# Nextronic-Arduino.net
KiCad netlist of a schematic drawn in EAGLE
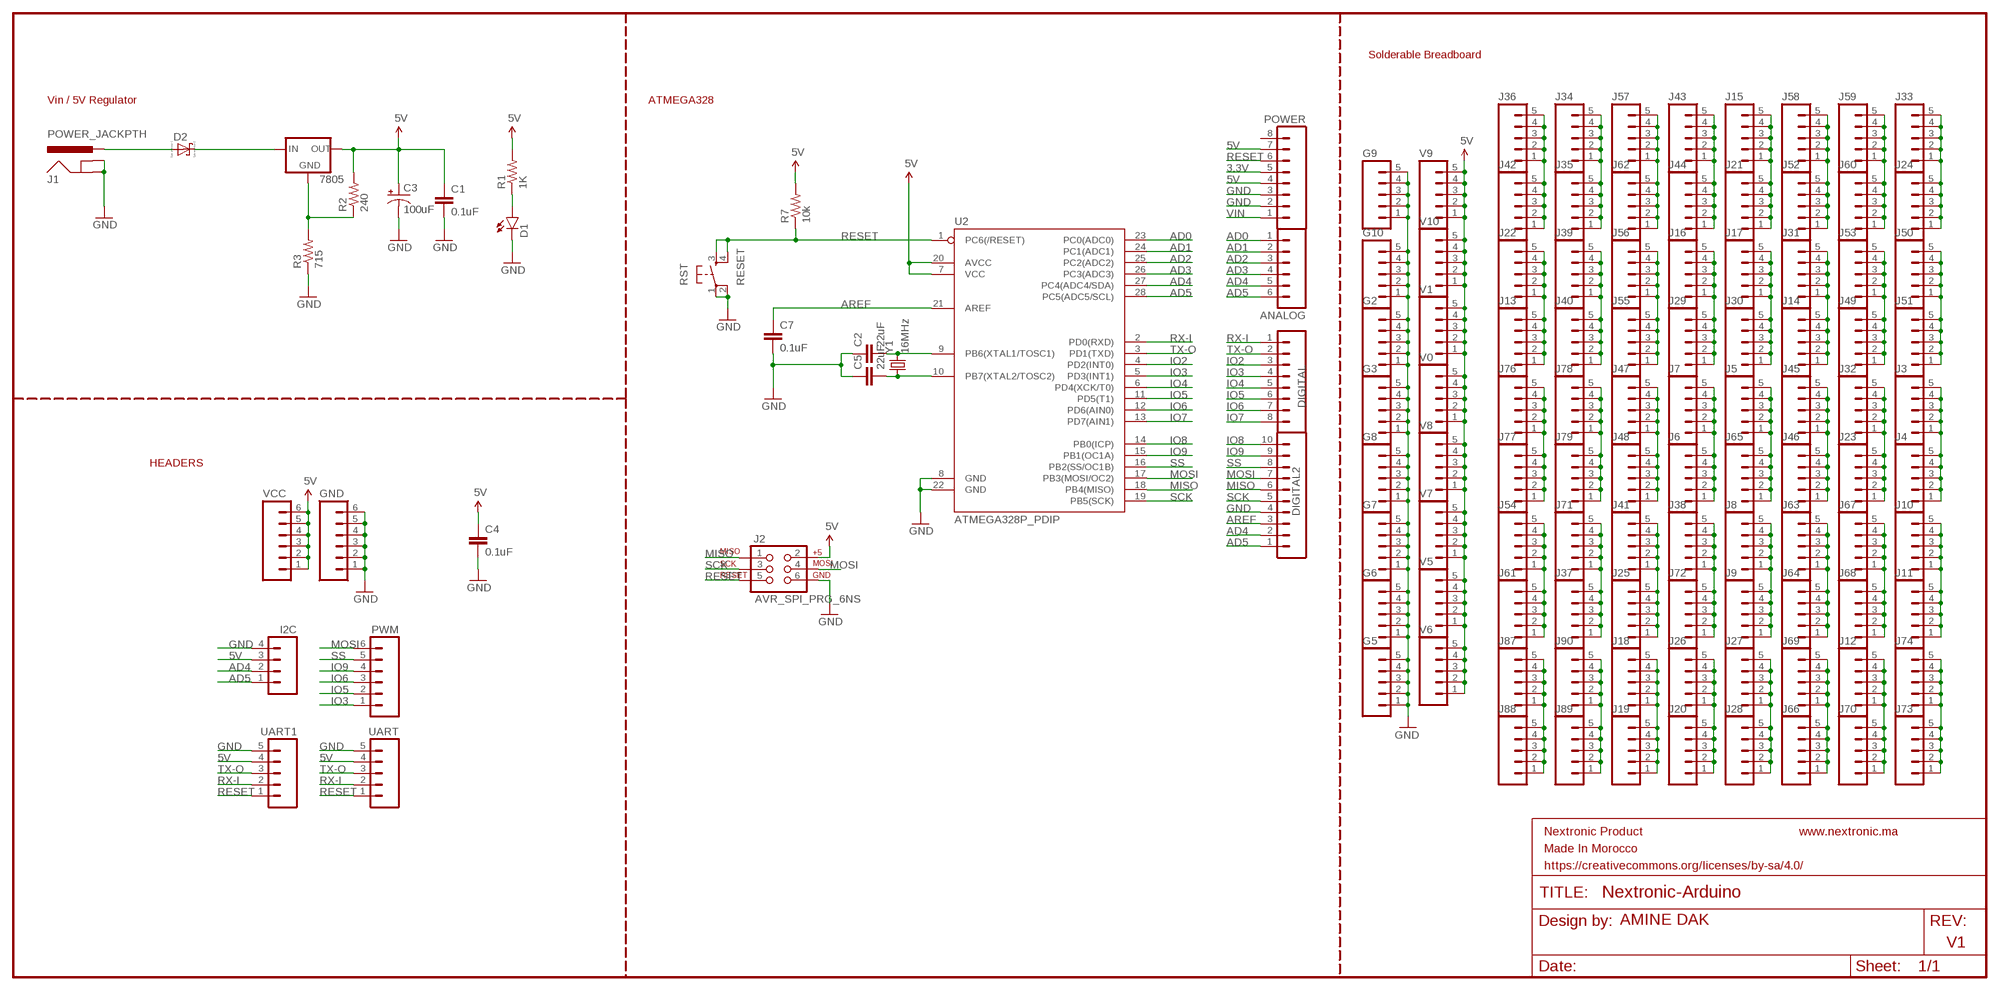
[diagram p0: schematic, sheet 1]

(export (version "E")
  (design (tool "Eeschema 10.0.6"))
  (components
    (comp (ref "7805")
      (value "V_REG_78XX-TO-220")
      (footprint "eagle-import:TO-220-ALT")
      (libsource (lib "eagle-import") (part "V_REG_78XX-TO-220"))
    )
    (comp (ref "ANALOG")
      (value "M06SILK_FEMALE_PTH")
      (footprint "eagle-import:1X06")
      (libsource (lib "eagle-import") (part "M06SILK_FEMALE_PTH"))
    )
    (comp (ref "C1")
      (value "0.1uF")
      (footprint "eagle-import:CAP-PTH-SMALLEZ")
      (fields (field (name "MF") "MULTICOMP") (field (name "MPN") "MCRR25104X7RK0050"))
      (libsource (lib "eagle-import") (part "CAPEZ"))
    )
    (comp (ref "C2")
      (value "22uF")
      (footprint "eagle-import:CAP-PTH-SMALLEZ")
      (fields (field (name "MF") "MULTICOMP") (field (name "MPN") "MCGPR100V226M8X11"))
      (libsource (lib "eagle-import") (part "CAPEZ"))
    )
    (comp (ref "C3")
      (value "100uF")
      (footprint "eagle-import:CPOL-RADIAL-100UF-25V")
      (fields (field (name "MF") "MULTICOMP") (field (name "MPN") "MCGPR25V107M6.3X11"))
      (libsource (lib "eagle-import") (part "CAP_POLPTH1"))
    )
    (comp (ref "C4")
      (value "0.1uF")
      (footprint "eagle-import:CAP-PTH-SMALLEZ")
      (fields (field (name "MF") "MULTICOMP") (field (name "MPN") "MCRR25104X7RK0050"))
      (libsource (lib "eagle-import") (part "CAPEZ"))
    )
    (comp (ref "C5")
      (value "22uF")
      (footprint "eagle-import:CAP-PTH-SMALLEZ")
      (fields (field (name "MF") "MULTICOMP") (field (name "MPN") "MCGPR100V226M8X11"))
      (libsource (lib "eagle-import") (part "CAPEZ"))
    )
    (comp (ref "C7")
      (value "0.1uF")
      (footprint "eagle-import:CAP-PTH-SMALLEZ")
      (fields (field (name "MF") "MULTICOMP") (field (name "MPN") "MCRR25104X7RK0050"))
      (libsource (lib "eagle-import") (part "CAPEZ"))
    )
    (comp (ref "D1")
      (value "LED-3MM-NO_SILK")
      (footprint "eagle-import:LED3MM-NS")
      (libsource (lib "eagle-import") (part "LED-3MM-NO_SILK"))
    )
    (comp (ref "D2")
      (value "SCHOTTKY-DIODEDO35-7")
      (footprint "eagle-import:DIODE_DO35-7")
      (libsource (lib "eagle-import") (part "SCHOTTKY-DIODEDO35-7"))
    )
    (comp (ref "DIGITAL")
      (value "M08SILK_FEMALE_PTH")
      (footprint "eagle-import:1X08")
      (libsource (lib "eagle-import") (part "M08SILK_FEMALE_PTH"))
    )
    (comp (ref "DIGITAL2")
      (value "M10SILK_FEMALE_PTH")
      (footprint "eagle-import:1X10")
      (libsource (lib "eagle-import") (part "M10SILK_FEMALE_PTH"))
    )
    (comp (ref "G2")
      (value "M05PTH")
      (footprint "eagle-import:1X05")
      (libsource (lib "eagle-import") (part "M05PTH"))
    )
    (comp (ref "G3")
      (value "M05PTH")
      (footprint "eagle-import:1X05")
      (libsource (lib "eagle-import") (part "M05PTH"))
    )
    (comp (ref "G5")
      (value "M05PTH")
      (footprint "eagle-import:1X05")
      (libsource (lib "eagle-import") (part "M05PTH"))
    )
    (comp (ref "G6")
      (value "M05PTH")
      (footprint "eagle-import:1X05")
      (libsource (lib "eagle-import") (part "M05PTH"))
    )
    (comp (ref "G7")
      (value "M05PTH")
      (footprint "eagle-import:1X05")
      (libsource (lib "eagle-import") (part "M05PTH"))
    )
    (comp (ref "G8")
      (value "M05PTH")
      (footprint "eagle-import:1X05")
      (libsource (lib "eagle-import") (part "M05PTH"))
    )
    (comp (ref "G9")
      (value "M05PTH")
      (footprint "eagle-import:1X05")
      (libsource (lib "eagle-import") (part "M05PTH"))
    )
    (comp (ref "G10")
      (value "M05PTH")
      (footprint "eagle-import:1X05")
      (libsource (lib "eagle-import") (part "M05PTH"))
    )
    (comp (ref "GND")
      (value "M06SILK_FEMALE_PTH")
      (footprint "eagle-import:1X06")
      (libsource (lib "eagle-import") (part "M06SILK_FEMALE_PTH"))
    )
    (comp (ref "I2C")
      (value "M04PTH")
      (footprint "eagle-import:1X04")
      (libsource (lib "eagle-import") (part "M04PTH"))
    )
    (comp (ref "J1")
      (value "POWER_JACKPTH")
      (footprint "eagle-import:POWER_JACK_PTH")
      (libsource (lib "eagle-import") (part "POWER_JACKPTH"))
    )
    (comp (ref "J2")
      (value "AVR_SPI_PRG_6NS")
      (footprint "eagle-import:2X3-NS")
      (libsource (lib "eagle-import") (part "AVR_SPI_PRG_6NS"))
    )
    (comp (ref "J3")
      (value "M05PTH")
      (footprint "eagle-import:1X05")
      (libsource (lib "eagle-import") (part "M05PTH"))
    )
    (comp (ref "J4")
      (value "M05PTH")
      (footprint "eagle-import:1X05")
      (libsource (lib "eagle-import") (part "M05PTH"))
    )
    (comp (ref "J5")
      (value "M05PTH")
      (footprint "eagle-import:1X05")
      (libsource (lib "eagle-import") (part "M05PTH"))
    )
    (comp (ref "J6")
      (value "M05PTH")
      (footprint "eagle-import:1X05")
      (libsource (lib "eagle-import") (part "M05PTH"))
    )
    (comp (ref "J7")
      (value "M05PTH")
      (footprint "eagle-import:1X05")
      (libsource (lib "eagle-import") (part "M05PTH"))
    )
    (comp (ref "J8")
      (value "M05PTH")
      (footprint "eagle-import:1X05")
      (libsource (lib "eagle-import") (part "M05PTH"))
    )
    (comp (ref "J9")
      (value "M05PTH")
      (footprint "eagle-import:1X05")
      (libsource (lib "eagle-import") (part "M05PTH"))
    )
    (comp (ref "J10")
      (value "M05PTH")
      (footprint "eagle-import:1X05")
      (libsource (lib "eagle-import") (part "M05PTH"))
    )
    (comp (ref "J11")
      (value "M05PTH")
      (footprint "eagle-import:1X05")
      (libsource (lib "eagle-import") (part "M05PTH"))
    )
    (comp (ref "J12")
      (value "M05PTH")
      (footprint "eagle-import:1X05")
      (libsource (lib "eagle-import") (part "M05PTH"))
    )
    (comp (ref "J13")
      (value "M05PTH")
      (footprint "eagle-import:1X05")
      (libsource (lib "eagle-import") (part "M05PTH"))
    )
    (comp (ref "J14")
      (value "M05PTH")
      (footprint "eagle-import:1X05")
      (libsource (lib "eagle-import") (part "M05PTH"))
    )
    (comp (ref "J15")
      (value "M05PTH")
      (footprint "eagle-import:1X05")
      (libsource (lib "eagle-import") (part "M05PTH"))
    )
    (comp (ref "J16")
      (value "M05PTH")
      (footprint "eagle-import:1X05")
      (libsource (lib "eagle-import") (part "M05PTH"))
    )
    (comp (ref "J17")
      (value "M05PTH")
      (footprint "eagle-import:1X05")
      (libsource (lib "eagle-import") (part "M05PTH"))
    )
    (comp (ref "J18")
      (value "M05PTH")
      (footprint "eagle-import:1X05")
      (libsource (lib "eagle-import") (part "M05PTH"))
    )
    (comp (ref "J19")
      (value "M05PTH")
      (footprint "eagle-import:1X05")
      (libsource (lib "eagle-import") (part "M05PTH"))
    )
    (comp (ref "J20")
      (value "M05PTH")
      (footprint "eagle-import:1X05")
      (libsource (lib "eagle-import") (part "M05PTH"))
    )
    (comp (ref "J21")
      (value "M05PTH")
      (footprint "eagle-import:1X05")
      (libsource (lib "eagle-import") (part "M05PTH"))
    )
    (comp (ref "J22")
      (value "M05PTH")
      (footprint "eagle-import:1X05")
      (libsource (lib "eagle-import") (part "M05PTH"))
    )
    (comp (ref "J23")
      (value "M05PTH")
      (footprint "eagle-import:1X05")
      (libsource (lib "eagle-import") (part "M05PTH"))
    )
    (comp (ref "J24")
      (value "M05PTH")
      (footprint "eagle-import:1X05")
      (libsource (lib "eagle-import") (part "M05PTH"))
    )
    (comp (ref "J25")
      (value "M05PTH")
      (footprint "eagle-import:1X05")
      (libsource (lib "eagle-import") (part "M05PTH"))
    )
    (comp (ref "J26")
      (value "M05PTH")
      (footprint "eagle-import:1X05")
      (libsource (lib "eagle-import") (part "M05PTH"))
    )
    (comp (ref "J27")
      (value "M05PTH")
      (footprint "eagle-import:1X05")
      (libsource (lib "eagle-import") (part "M05PTH"))
    )
    (comp (ref "J28")
      (value "M05PTH")
      (footprint "eagle-import:1X05")
      (libsource (lib "eagle-import") (part "M05PTH"))
    )
    (comp (ref "J29")
      (value "M05PTH")
      (footprint "eagle-import:1X05")
      (libsource (lib "eagle-import") (part "M05PTH"))
    )
    (comp (ref "J30")
      (value "M05PTH")
      (footprint "eagle-import:1X05")
      (libsource (lib "eagle-import") (part "M05PTH"))
    )
    (comp (ref "J31")
      (value "M05PTH")
      (footprint "eagle-import:1X05")
      (libsource (lib "eagle-import") (part "M05PTH"))
    )
    (comp (ref "J32")
      (value "M05PTH")
      (footprint "eagle-import:1X05")
      (libsource (lib "eagle-import") (part "M05PTH"))
    )
    (comp (ref "J33")
      (value "M05PTH")
      (footprint "eagle-import:1X05")
      (libsource (lib "eagle-import") (part "M05PTH"))
    )
    (comp (ref "J34")
      (value "M05PTH")
      (footprint "eagle-import:1X05")
      (libsource (lib "eagle-import") (part "M05PTH"))
    )
    (comp (ref "J35")
      (value "M05PTH")
      (footprint "eagle-import:1X05")
      (libsource (lib "eagle-import") (part "M05PTH"))
    )
    (comp (ref "J36")
      (value "M05PTH")
      (footprint "eagle-import:1X05")
      (libsource (lib "eagle-import") (part "M05PTH"))
    )
    (comp (ref "J37")
      (value "M05PTH")
      (footprint "eagle-import:1X05")
      (libsource (lib "eagle-import") (part "M05PTH"))
    )
    (comp (ref "J38")
      (value "M05PTH")
      (footprint "eagle-import:1X05")
      (libsource (lib "eagle-import") (part "M05PTH"))
    )
    (comp (ref "J39")
      (value "M05PTH")
      (footprint "eagle-import:1X05")
      (libsource (lib "eagle-import") (part "M05PTH"))
    )
    (comp (ref "J40")
      (value "M05PTH")
      (footprint "eagle-import:1X05")
      (libsource (lib "eagle-import") (part "M05PTH"))
    )
    (comp (ref "J41")
      (value "M05PTH")
      (footprint "eagle-import:1X05")
      (libsource (lib "eagle-import") (part "M05PTH"))
    )
    (comp (ref "J42")
      (value "M05PTH")
      (footprint "eagle-import:1X05")
      (libsource (lib "eagle-import") (part "M05PTH"))
    )
    (comp (ref "J43")
      (value "M05PTH")
      (footprint "eagle-import:1X05")
      (libsource (lib "eagle-import") (part "M05PTH"))
    )
    (comp (ref "J44")
      (value "M05PTH")
      (footprint "eagle-import:1X05")
      (libsource (lib "eagle-import") (part "M05PTH"))
    )
    (comp (ref "J45")
      (value "M05PTH")
      (footprint "eagle-import:1X05")
      (libsource (lib "eagle-import") (part "M05PTH"))
    )
    (comp (ref "J46")
      (value "M05PTH")
      (footprint "eagle-import:1X05")
      (libsource (lib "eagle-import") (part "M05PTH"))
    )
    (comp (ref "J47")
      (value "M05PTH")
      (footprint "eagle-import:1X05")
      (libsource (lib "eagle-import") (part "M05PTH"))
    )
    (comp (ref "J48")
      (value "M05PTH")
      (footprint "eagle-import:1X05")
      (libsource (lib "eagle-import") (part "M05PTH"))
    )
    (comp (ref "J49")
      (value "M05PTH")
      (footprint "eagle-import:1X05")
      (libsource (lib "eagle-import") (part "M05PTH"))
    )
    (comp (ref "J50")
      (value "M05PTH")
      (footprint "eagle-import:1X05")
      (libsource (lib "eagle-import") (part "M05PTH"))
    )
    (comp (ref "J51")
      (value "M05PTH")
      (footprint "eagle-import:1X05")
      (libsource (lib "eagle-import") (part "M05PTH"))
    )
    (comp (ref "J52")
      (value "M05PTH")
      (footprint "eagle-import:1X05")
      (libsource (lib "eagle-import") (part "M05PTH"))
    )
    (comp (ref "J53")
      (value "M05PTH")
      (footprint "eagle-import:1X05")
      (libsource (lib "eagle-import") (part "M05PTH"))
    )
    (comp (ref "J54")
      (value "M05PTH")
      (footprint "eagle-import:1X05")
      (libsource (lib "eagle-import") (part "M05PTH"))
    )
    (comp (ref "J55")
      (value "M05PTH")
      (footprint "eagle-import:1X05")
      (libsource (lib "eagle-import") (part "M05PTH"))
    )
    (comp (ref "J56")
      (value "M05PTH")
      (footprint "eagle-import:1X05")
      (libsource (lib "eagle-import") (part "M05PTH"))
    )
    (comp (ref "J57")
      (value "M05PTH")
      (footprint "eagle-import:1X05")
      (libsource (lib "eagle-import") (part "M05PTH"))
    )
    (comp (ref "J58")
      (value "M05PTH")
      (footprint "eagle-import:1X05")
      (libsource (lib "eagle-import") (part "M05PTH"))
    )
    (comp (ref "J59")
      (value "M05PTH")
      (footprint "eagle-import:1X05")
      (libsource (lib "eagle-import") (part "M05PTH"))
    )
    (comp (ref "J60")
      (value "M05PTH")
      (footprint "eagle-import:1X05")
      (libsource (lib "eagle-import") (part "M05PTH"))
    )
    (comp (ref "J61")
      (value "M05PTH")
      (footprint "eagle-import:1X05")
      (libsource (lib "eagle-import") (part "M05PTH"))
    )
    (comp (ref "J62")
      (value "M05PTH")
      (footprint "eagle-import:1X05")
      (libsource (lib "eagle-import") (part "M05PTH"))
    )
    (comp (ref "J63")
      (value "M05PTH")
      (footprint "eagle-import:1X05")
      (libsource (lib "eagle-import") (part "M05PTH"))
    )
    (comp (ref "J64")
      (value "M05PTH")
      (footprint "eagle-import:1X05")
      (libsource (lib "eagle-import") (part "M05PTH"))
    )
    (comp (ref "J65")
      (value "M05PTH")
      (footprint "eagle-import:1X05")
      (libsource (lib "eagle-import") (part "M05PTH"))
    )
    (comp (ref "J66")
      (value "M05PTH")
      (footprint "eagle-import:1X05")
      (libsource (lib "eagle-import") (part "M05PTH"))
    )
    (comp (ref "J67")
      (value "M05PTH")
      (footprint "eagle-import:1X05")
      (libsource (lib "eagle-import") (part "M05PTH"))
    )
    (comp (ref "J68")
      (value "M05PTH")
      (footprint "eagle-import:1X05")
      (libsource (lib "eagle-import") (part "M05PTH"))
    )
    (comp (ref "J69")
      (value "M05PTH")
      (footprint "eagle-import:1X05")
      (libsource (lib "eagle-import") (part "M05PTH"))
    )
    (comp (ref "J70")
      (value "M05PTH")
      (footprint "eagle-import:1X05")
      (libsource (lib "eagle-import") (part "M05PTH"))
    )
    (comp (ref "J71")
      (value "M05PTH")
      (footprint "eagle-import:1X05")
      (libsource (lib "eagle-import") (part "M05PTH"))
    )
    (comp (ref "J72")
      (value "M05PTH")
      (footprint "eagle-import:1X05")
      (libsource (lib "eagle-import") (part "M05PTH"))
    )
    (comp (ref "J73")
      (value "M05PTH")
      (footprint "eagle-import:1X05")
      (libsource (lib "eagle-import") (part "M05PTH"))
    )
    (comp (ref "J74")
      (value "M05PTH")
      (footprint "eagle-import:1X05")
      (libsource (lib "eagle-import") (part "M05PTH"))
    )
    (comp (ref "J76")
      (value "M05PTH")
      (footprint "eagle-import:1X05")
      (libsource (lib "eagle-import") (part "M05PTH"))
    )
    (comp (ref "J77")
      (value "M05PTH")
      (footprint "eagle-import:1X05")
      (libsource (lib "eagle-import") (part "M05PTH"))
    )
    (comp (ref "J78")
      (value "M05PTH")
      (footprint "eagle-import:1X05")
      (libsource (lib "eagle-import") (part "M05PTH"))
    )
    (comp (ref "J79")
      (value "M05PTH")
      (footprint "eagle-import:1X05")
      (libsource (lib "eagle-import") (part "M05PTH"))
    )
    (comp (ref "J87")
      (value "M05PTH")
      (footprint "eagle-import:1X05")
      (libsource (lib "eagle-import") (part "M05PTH"))
    )
    (comp (ref "J88")
      (value "M05PTH")
      (footprint "eagle-import:1X05")
      (libsource (lib "eagle-import") (part "M05PTH"))
    )
    (comp (ref "J89")
      (value "M05PTH")
      (footprint "eagle-import:1X05")
      (libsource (lib "eagle-import") (part "M05PTH"))
    )
    (comp (ref "J90")
      (value "M05PTH")
      (footprint "eagle-import:1X05")
      (libsource (lib "eagle-import") (part "M05PTH"))
    )
    (comp (ref "POWER")
      (value "M08SILK_FEMALE_PTH")
      (footprint "eagle-import:1X08")
      (libsource (lib "eagle-import") (part "M08SILK_FEMALE_PTH"))
    )
    (comp (ref "PWM")
      (value "M06SILK_FEMALE_PTH")
      (footprint "eagle-import:1X06")
      (libsource (lib "eagle-import") (part "M06SILK_FEMALE_PTH"))
    )
    (comp (ref "R1")
      (value "1K")
      (footprint "eagle-import:AXIAL-0.3")
      (fields (field (name "MF") "MULTICOMP") (field (name "MPN") "MCRE000037"))
      (libsource (lib "eagle-import") (part "RESISTORAXIAL-0.3"))
    )
    (comp (ref "R2")
      (value "240")
      (footprint "eagle-import:AXIAL-0.3")
      (fields (field (name "MF") "WELWYN") (field (name "MPN") "MFR4-240RFI"))
      (libsource (lib "eagle-import") (part "RESISTORAXIAL-0.3"))
    )
    (comp (ref "R3")
      (value "715")
      (footprint "eagle-import:AXIAL-0.3")
      (fields (field (name "MF") "TE CONNECTIVITY / NEOHM") (field (name "MPN") "YR1B715RCC"))
      (libsource (lib "eagle-import") (part "RESISTORAXIAL-0.3"))
    )
    (comp (ref "R7")
      (value "10k")
      (footprint "eagle-import:AXIAL-0.3")
      (libsource (lib "eagle-import") (part "RESISTORAXIAL-0.3"))
    )
    (comp (ref "RST")
      (value "RESET")
      (footprint "eagle-import:TACTILE-PTH")
      (libsource (lib "eagle-import") (part "TAC_SWITCHPTH"))
    )
    (comp (ref "U2")
      (value "ATMEGA328P_PDIP")
      (footprint "eagle-import:DIL28-3")
      (fields (field (name "MF") "ATMEL") (field (name "MPN") "ATMEGA328-PU"))
      (libsource (lib "eagle-import") (part "ATMEGA328P_PDIP"))
    )
    (comp (ref "UART")
      (value "M05PTH")
      (footprint "eagle-import:1X05")
      (libsource (lib "eagle-import") (part "M05PTH"))
    )
    (comp (ref "UART1")
      (value "M05PTH")
      (footprint "eagle-import:1X05")
      (libsource (lib "eagle-import") (part "M05PTH"))
    )
    (comp (ref "V0")
      (value "M05PTH")
      (footprint "eagle-import:1X05")
      (libsource (lib "eagle-import") (part "M05PTH"))
    )
    (comp (ref "V1")
      (value "M05PTH")
      (footprint "eagle-import:1X05")
      (libsource (lib "eagle-import") (part "M05PTH"))
    )
    (comp (ref "V5")
      (value "M05PTH")
      (footprint "eagle-import:1X05")
      (libsource (lib "eagle-import") (part "M05PTH"))
    )
    (comp (ref "V6")
      (value "M05PTH")
      (footprint "eagle-import:1X05")
      (libsource (lib "eagle-import") (part "M05PTH"))
    )
    (comp (ref "V7")
      (value "M05PTH")
      (footprint "eagle-import:1X05")
      (libsource (lib "eagle-import") (part "M05PTH"))
    )
    (comp (ref "V8")
      (value "M05PTH")
      (footprint "eagle-import:1X05")
      (libsource (lib "eagle-import") (part "M05PTH"))
    )
    (comp (ref "V9")
      (value "M05PTH")
      (footprint "eagle-import:1X05")
      (libsource (lib "eagle-import") (part "M05PTH"))
    )
    (comp (ref "V10")
      (value "M05PTH")
      (footprint "eagle-import:1X05")
      (libsource (lib "eagle-import") (part "M05PTH"))
    )
    (comp (ref "VCC")
      (value "M06SILK_FEMALE_PTH")
      (footprint "eagle-import:1X06")
      (libsource (lib "eagle-import") (part "M06SILK_FEMALE_PTH"))
    )
    (comp (ref "Y1")
      (value "16MHz")
      (footprint "eagle-import:HC49US")
      (fields (field (name "MF") "RALTRON") (field (name "MPN") "AS-16.000-18"))
      (libsource (lib "eagle-import") (part "CRYSTALHC49US"))
    )
  )
  (nets
    (net (code "1") (name "/3.3V") (class "Default")
      (node (ref "POWER") (pin "5") (pinfunction "5_5") (pintype "passive"))
    )
    (net (code "2") (name "/AD0") (class "Default")
      (node (ref "ANALOG") (pin "1") (pinfunction "1_1") (pintype "passive"))
      (node (ref "U2") (pin "23") (pinfunction "PC0(ADC0)_23") (pintype "bidirectional"))
    )
    (net (code "3") (name "/AD1") (class "Default")
      (node (ref "ANALOG") (pin "2") (pinfunction "2_2") (pintype "passive"))
      (node (ref "U2") (pin "24") (pinfunction "PC1(ADC1)_24") (pintype "bidirectional"))
    )
    (net (code "4") (name "/AD2") (class "Default")
      (node (ref "ANALOG") (pin "3") (pinfunction "3_3") (pintype "passive"))
      (node (ref "U2") (pin "25") (pinfunction "PC2(ADC2)_25") (pintype "bidirectional"))
    )
    (net (code "5") (name "/AD3") (class "Default")
      (node (ref "ANALOG") (pin "4") (pinfunction "4_4") (pintype "passive"))
      (node (ref "U2") (pin "26") (pinfunction "PC3(ADC3)_26") (pintype "bidirectional"))
    )
    (net (code "6") (name "/AD4") (class "Default")
      (node (ref "ANALOG") (pin "5") (pinfunction "5_5") (pintype "passive"))
      (node (ref "DIGITAL2") (pin "2") (pinfunction "2_2") (pintype "passive"))
      (node (ref "I2C") (pin "2") (pinfunction "2_2") (pintype "passive"))
      (node (ref "U2") (pin "27") (pinfunction "PC4(ADC4/SDA)_27") (pintype "bidirectional"))
    )
    (net (code "7") (name "/AD5") (class "Default")
      (node (ref "ANALOG") (pin "6") (pinfunction "6_6") (pintype "passive"))
      (node (ref "DIGITAL2") (pin "1") (pinfunction "1_1") (pintype "passive"))
      (node (ref "I2C") (pin "1") (pinfunction "1_1") (pintype "passive"))
      (node (ref "U2") (pin "28") (pinfunction "PC5(ADC5/SCL)_28") (pintype "bidirectional"))
    )
    (net (code "8") (name "/AREF") (class "Default")
      (node (ref "C7") (pin "1") (pinfunction "1_1") (pintype "passive"))
      (node (ref "DIGITAL2") (pin "3") (pinfunction "3_3") (pintype "passive"))
      (node (ref "U2") (pin "21") (pinfunction "AREF_21") (pintype "bidirectional"))
    )
    (net (code "9") (name "/IO2") (class "Default")
      (node (ref "DIGITAL") (pin "3") (pinfunction "3_3") (pintype "passive"))
      (node (ref "U2") (pin "4") (pinfunction "PD2(INT0)_4") (pintype "bidirectional"))
    )
    (net (code "10") (name "/IO3") (class "Default")
      (node (ref "DIGITAL") (pin "4") (pinfunction "4_4") (pintype "passive"))
      (node (ref "PWM") (pin "1") (pinfunction "1_1") (pintype "passive"))
      (node (ref "U2") (pin "5") (pinfunction "PD3(INT1)_5") (pintype "bidirectional"))
    )
    (net (code "11") (name "/IO4") (class "Default")
      (node (ref "DIGITAL") (pin "5") (pinfunction "5_5") (pintype "passive"))
      (node (ref "U2") (pin "6") (pinfunction "PD4(XCK/T0)_6") (pintype "bidirectional"))
    )
    (net (code "12") (name "/IO5") (class "Default")
      (node (ref "DIGITAL") (pin "6") (pinfunction "6_6") (pintype "passive"))
      (node (ref "PWM") (pin "2") (pinfunction "2_2") (pintype "passive"))
      (node (ref "U2") (pin "11") (pinfunction "PD5(T1)_11") (pintype "bidirectional"))
    )
    (net (code "13") (name "/IO6") (class "Default")
      (node (ref "DIGITAL") (pin "7") (pinfunction "7_7") (pintype "passive"))
      (node (ref "PWM") (pin "3") (pinfunction "3_3") (pintype "passive"))
      (node (ref "U2") (pin "12") (pinfunction "PD6(AIN0)_12") (pintype "bidirectional"))
    )
    (net (code "14") (name "/IO7") (class "Default")
      (node (ref "DIGITAL") (pin "8") (pinfunction "8_8") (pintype "passive"))
      (node (ref "U2") (pin "13") (pinfunction "PD7(AIN1)_13") (pintype "bidirectional"))
    )
    (net (code "15") (name "/IO8") (class "Default")
      (node (ref "DIGITAL2") (pin "10") (pinfunction "10_10") (pintype "passive"))
      (node (ref "U2") (pin "14") (pinfunction "PB0(ICP)_14") (pintype "bidirectional"))
    )
    (net (code "16") (name "/IO9") (class "Default")
      (node (ref "DIGITAL2") (pin "9") (pinfunction "9_9") (pintype "passive"))
      (node (ref "PWM") (pin "4") (pinfunction "4_4") (pintype "passive"))
      (node (ref "U2") (pin "15") (pinfunction "PB1(OC1A)_15") (pintype "bidirectional"))
    )
    (net (code "17") (name "/MISO") (class "Default")
      (node (ref "DIGITAL2") (pin "6") (pinfunction "6_6") (pintype "passive"))
      (node (ref "J2") (pin "1") (pinfunction "1_1") (pintype "passive"))
      (node (ref "U2") (pin "18") (pinfunction "PB4(MISO)_18") (pintype "bidirectional"))
    )
    (net (code "18") (name "/MOSI") (class "Default")
      (node (ref "DIGITAL2") (pin "7") (pinfunction "7_7") (pintype "passive"))
      (node (ref "J2") (pin "4") (pinfunction "4_4") (pintype "passive"))
      (node (ref "PWM") (pin "6") (pinfunction "6_6") (pintype "passive"))
      (node (ref "U2") (pin "17") (pinfunction "PB3(MOSI/OC2)_17") (pintype "bidirectional"))
    )
    (net (code "19") (name "/RESET") (class "Default")
      (node (ref "J2") (pin "5") (pinfunction "5_5") (pintype "passive"))
      (node (ref "POWER") (pin "6") (pinfunction "6_6") (pintype "passive"))
      (node (ref "R7") (pin "P$1") (pinfunction "1_P$1") (pintype "passive"))
      (node (ref "RST") (pin "3") (pinfunction "3_3") (pintype "passive"))
      (node (ref "RST") (pin "4") (pinfunction "4_4") (pintype "passive"))
      (node (ref "U2") (pin "1") (pinfunction "PC6(/RESET)_1") (pintype "bidirectional"))
      (node (ref "UART") (pin "1") (pinfunction "1_1") (pintype "passive"))
      (node (ref "UART1") (pin "1") (pinfunction "1_1") (pintype "passive"))
    )
    (net (code "20") (name "/RX-I") (class "Default")
      (node (ref "DIGITAL") (pin "1") (pinfunction "1_1") (pintype "passive"))
      (node (ref "U2") (pin "2") (pinfunction "PD0(RXD)_2") (pintype "bidirectional"))
      (node (ref "UART") (pin "2") (pinfunction "2_2") (pintype "passive"))
      (node (ref "UART1") (pin "2") (pinfunction "2_2") (pintype "passive"))
    )
    (net (code "21") (name "/SCK") (class "Default")
      (node (ref "DIGITAL2") (pin "5") (pinfunction "5_5") (pintype "passive"))
      (node (ref "J2") (pin "3") (pinfunction "3_3") (pintype "passive"))
      (node (ref "U2") (pin "19") (pinfunction "PB5(SCK)_19") (pintype "bidirectional"))
    )
    (net (code "22") (name "/SS") (class "Default")
      (node (ref "DIGITAL2") (pin "8") (pinfunction "8_8") (pintype "passive"))
      (node (ref "PWM") (pin "5") (pinfunction "5_5") (pintype "passive"))
      (node (ref "U2") (pin "16") (pinfunction "PB2(SS/OC1B)_16") (pintype "bidirectional"))
    )
    (net (code "23") (name "/TX-O") (class "Default")
      (node (ref "DIGITAL") (pin "2") (pinfunction "2_2") (pintype "passive"))
      (node (ref "U2") (pin "3") (pinfunction "PD1(TXD)_3") (pintype "bidirectional"))
      (node (ref "UART") (pin "3") (pinfunction "3_3") (pintype "passive"))
      (node (ref "UART1") (pin "3") (pinfunction "3_3") (pintype "passive"))
    )
    (net (code "24") (name "/VIN") (class "Default")
      (node (ref "POWER") (pin "1") (pinfunction "1_1") (pintype "passive"))
    )
    (net (code "25") (name "5V") (class "Default")
      (node (ref "7805") (pin "OUT") (pinfunction "OUT_OUT") (pintype "passive"))
      (node (ref "C1") (pin "1") (pinfunction "1_1") (pintype "passive"))
      (node (ref "C3") (pin "1") (pinfunction "+_1") (pintype "passive"))
      (node (ref "C4") (pin "1") (pinfunction "1_1") (pintype "passive"))
      (node (ref "I2C") (pin "3") (pinfunction "3_3") (pintype "passive"))
      (node (ref "J2") (pin "2") (pinfunction "2_2") (pintype "passive"))
      (node (ref "POWER") (pin "4") (pinfunction "4_4") (pintype "passive"))
      (node (ref "POWER") (pin "7") (pinfunction "7_7") (pintype "passive"))
      (node (ref "R1") (pin "P$2") (pinfunction "2_P$2") (pintype "passive"))
      (node (ref "R2") (pin "P$2") (pinfunction "2_P$2") (pintype "passive"))
      (node (ref "R7") (pin "P$2") (pinfunction "2_P$2") (pintype "passive"))
      (node (ref "U2") (pin "20") (pinfunction "AVCC_20") (pintype "bidirectional"))
      (node (ref "U2") (pin "7") (pinfunction "VCC_7") (pintype "bidirectional"))
      (node (ref "UART") (pin "4") (pinfunction "4_4") (pintype "passive"))
      (node (ref "UART1") (pin "4") (pinfunction "4_4") (pintype "passive"))
      (node (ref "V0") (pin "1") (pinfunction "1_1") (pintype "passive"))
      (node (ref "V0") (pin "2") (pinfunction "2_2") (pintype "passive"))
      (node (ref "V0") (pin "3") (pinfunction "3_3") (pintype "passive"))
      (node (ref "V0") (pin "4") (pinfunction "4_4") (pintype "passive"))
      (node (ref "V0") (pin "5") (pinfunction "5_5") (pintype "passive"))
      (node (ref "V1") (pin "1") (pinfunction "1_1") (pintype "passive"))
      (node (ref "V1") (pin "2") (pinfunction "2_2") (pintype "passive"))
      (node (ref "V1") (pin "3") (pinfunction "3_3") (pintype "passive"))
      (node (ref "V1") (pin "4") (pinfunction "4_4") (pintype "passive"))
      (node (ref "V1") (pin "5") (pinfunction "5_5") (pintype "passive"))
      (node (ref "V10") (pin "1") (pinfunction "1_1") (pintype "passive"))
      (node (ref "V10") (pin "2") (pinfunction "2_2") (pintype "passive"))
      (node (ref "V10") (pin "3") (pinfunction "3_3") (pintype "passive"))
      (node (ref "V10") (pin "4") (pinfunction "4_4") (pintype "passive"))
      (node (ref "V10") (pin "5") (pinfunction "5_5") (pintype "passive"))
      (node (ref "V5") (pin "1") (pinfunction "1_1") (pintype "passive"))
      (node (ref "V5") (pin "2") (pinfunction "2_2") (pintype "passive"))
      (node (ref "V5") (pin "3") (pinfunction "3_3") (pintype "passive"))
      (node (ref "V5") (pin "4") (pinfunction "4_4") (pintype "passive"))
      (node (ref "V5") (pin "5") (pinfunction "5_5") (pintype "passive"))
      (node (ref "V6") (pin "1") (pinfunction "1_1") (pintype "passive"))
      (node (ref "V6") (pin "2") (pinfunction "2_2") (pintype "passive"))
      (node (ref "V6") (pin "3") (pinfunction "3_3") (pintype "passive"))
      (node (ref "V6") (pin "4") (pinfunction "4_4") (pintype "passive"))
      (node (ref "V6") (pin "5") (pinfunction "5_5") (pintype "passive"))
      (node (ref "V7") (pin "1") (pinfunction "1_1") (pintype "passive"))
      (node (ref "V7") (pin "2") (pinfunction "2_2") (pintype "passive"))
      (node (ref "V7") (pin "3") (pinfunction "3_3") (pintype "passive"))
      (node (ref "V7") (pin "4") (pinfunction "4_4") (pintype "passive"))
      (node (ref "V7") (pin "5") (pinfunction "5_5") (pintype "passive"))
      (node (ref "V8") (pin "1") (pinfunction "1_1") (pintype "passive"))
      (node (ref "V8") (pin "2") (pinfunction "2_2") (pintype "passive"))
      (node (ref "V8") (pin "3") (pinfunction "3_3") (pintype "passive"))
      (node (ref "V8") (pin "4") (pinfunction "4_4") (pintype "passive"))
      (node (ref "V8") (pin "5") (pinfunction "5_5") (pintype "passive"))
      (node (ref "V9") (pin "1") (pinfunction "1_1") (pintype "passive"))
      (node (ref "V9") (pin "2") (pinfunction "2_2") (pintype "passive"))
      (node (ref "V9") (pin "3") (pinfunction "3_3") (pintype "passive"))
      (node (ref "V9") (pin "4") (pinfunction "4_4") (pintype "passive"))
      (node (ref "V9") (pin "5") (pinfunction "5_5") (pintype "passive"))
      (node (ref "VCC") (pin "1") (pinfunction "1_1") (pintype "passive"))
      (node (ref "VCC") (pin "2") (pinfunction "2_2") (pintype "passive"))
      (node (ref "VCC") (pin "3") (pinfunction "3_3") (pintype "passive"))
      (node (ref "VCC") (pin "4") (pinfunction "4_4") (pintype "passive"))
      (node (ref "VCC") (pin "5") (pinfunction "5_5") (pintype "passive"))
      (node (ref "VCC") (pin "6") (pinfunction "6_6") (pintype "passive"))
    )
    (net (code "26") (name "GND") (class "Default")
      (node (ref "C1") (pin "2") (pinfunction "2_2") (pintype "passive"))
      (node (ref "C2") (pin "1") (pinfunction "1_1") (pintype "passive"))
      (node (ref "C3") (pin "2") (pinfunction "-_2") (pintype "passive"))
      (node (ref "C4") (pin "2") (pinfunction "2_2") (pintype "passive"))
      (node (ref "C5") (pin "1") (pinfunction "1_1") (pintype "passive"))
      (node (ref "C7") (pin "2") (pinfunction "2_2") (pintype "passive"))
      (node (ref "D1") (pin "K") (pinfunction "C_K") (pintype "passive"))
      (node (ref "DIGITAL2") (pin "4") (pinfunction "4_4") (pintype "passive"))
      (node (ref "G10") (pin "1") (pinfunction "1_1") (pintype "passive"))
      (node (ref "G10") (pin "2") (pinfunction "2_2") (pintype "passive"))
      (node (ref "G10") (pin "3") (pinfunction "3_3") (pintype "passive"))
      (node (ref "G10") (pin "4") (pinfunction "4_4") (pintype "passive"))
      (node (ref "G10") (pin "5") (pinfunction "5_5") (pintype "passive"))
      (node (ref "G2") (pin "1") (pinfunction "1_1") (pintype "passive"))
      (node (ref "G2") (pin "2") (pinfunction "2_2") (pintype "passive"))
      (node (ref "G2") (pin "3") (pinfunction "3_3") (pintype "passive"))
      (node (ref "G2") (pin "4") (pinfunction "4_4") (pintype "passive"))
      (node (ref "G2") (pin "5") (pinfunction "5_5") (pintype "passive"))
      (node (ref "G3") (pin "1") (pinfunction "1_1") (pintype "passive"))
      (node (ref "G3") (pin "2") (pinfunction "2_2") (pintype "passive"))
      (node (ref "G3") (pin "3") (pinfunction "3_3") (pintype "passive"))
      (node (ref "G3") (pin "4") (pinfunction "4_4") (pintype "passive"))
      (node (ref "G3") (pin "5") (pinfunction "5_5") (pintype "passive"))
      (node (ref "G5") (pin "1") (pinfunction "1_1") (pintype "passive"))
      (node (ref "G5") (pin "2") (pinfunction "2_2") (pintype "passive"))
      (node (ref "G5") (pin "3") (pinfunction "3_3") (pintype "passive"))
      (node (ref "G5") (pin "4") (pinfunction "4_4") (pintype "passive"))
      (node (ref "G5") (pin "5") (pinfunction "5_5") (pintype "passive"))
      (node (ref "G6") (pin "1") (pinfunction "1_1") (pintype "passive"))
      (node (ref "G6") (pin "2") (pinfunction "2_2") (pintype "passive"))
      (node (ref "G6") (pin "3") (pinfunction "3_3") (pintype "passive"))
      (node (ref "G6") (pin "4") (pinfunction "4_4") (pintype "passive"))
      (node (ref "G6") (pin "5") (pinfunction "5_5") (pintype "passive"))
      (node (ref "G7") (pin "1") (pinfunction "1_1") (pintype "passive"))
      (node (ref "G7") (pin "2") (pinfunction "2_2") (pintype "passive"))
      (node (ref "G7") (pin "3") (pinfunction "3_3") (pintype "passive"))
      (node (ref "G7") (pin "4") (pinfunction "4_4") (pintype "passive"))
      (node (ref "G7") (pin "5") (pinfunction "5_5") (pintype "passive"))
      (node (ref "G8") (pin "1") (pinfunction "1_1") (pintype "passive"))
      (node (ref "G8") (pin "2") (pinfunction "2_2") (pintype "passive"))
      (node (ref "G8") (pin "3") (pinfunction "3_3") (pintype "passive"))
      (node (ref "G8") (pin "4") (pinfunction "4_4") (pintype "passive"))
      (node (ref "G8") (pin "5") (pinfunction "5_5") (pintype "passive"))
      (node (ref "G9") (pin "1") (pinfunction "1_1") (pintype "passive"))
      (node (ref "G9") (pin "2") (pinfunction "2_2") (pintype "passive"))
      (node (ref "G9") (pin "3") (pinfunction "3_3") (pintype "passive"))
      (node (ref "G9") (pin "4") (pinfunction "4_4") (pintype "passive"))
      (node (ref "G9") (pin "5") (pinfunction "5_5") (pintype "passive"))
      (node (ref "GND") (pin "1") (pinfunction "1_1") (pintype "passive"))
      (node (ref "GND") (pin "2") (pinfunction "2_2") (pintype "passive"))
      (node (ref "GND") (pin "3") (pinfunction "3_3") (pintype "passive"))
      (node (ref "GND") (pin "4") (pinfunction "4_4") (pintype "passive"))
      (node (ref "GND") (pin "5") (pinfunction "5_5") (pintype "passive"))
      (node (ref "GND") (pin "6") (pinfunction "6_6") (pintype "passive"))
      (node (ref "I2C") (pin "4") (pinfunction "4_4") (pintype "passive"))
      (node (ref "J1") (pin "GND") (pinfunction "GND_GND") (pintype "bidirectional"))
      (node (ref "J1") (pin "GNDBREAK") (pinfunction "GNDBREAK_GNDBREAK") (pintype "bidirectional"))
      (node (ref "J2") (pin "6") (pinfunction "6_6") (pintype "passive"))
      (node (ref "POWER") (pin "2") (pinfunction "2_2") (pintype "passive"))
      (node (ref "POWER") (pin "3") (pinfunction "3_3") (pintype "passive"))
      (node (ref "R3") (pin "P$1") (pinfunction "1_P$1") (pintype "passive"))
      (node (ref "RST") (pin "1") (pinfunction "1_1") (pintype "passive"))
      (node (ref "RST") (pin "2") (pinfunction "2_2") (pintype "passive"))
      (node (ref "U2") (pin "22") (pinfunction "GND_22") (pintype "bidirectional"))
      (node (ref "U2") (pin "8") (pinfunction "GND_8") (pintype "bidirectional"))
      (node (ref "UART") (pin "5") (pinfunction "5_5") (pintype "passive"))
      (node (ref "UART1") (pin "5") (pinfunction "5_5") (pintype "passive"))
    )
    (net (code "27") (name "Net-(D2-A)") (class "Default")
      (node (ref "7805") (pin "IN") (pinfunction "IN_IN") (pintype "input"))
      (node (ref "D2") (pin "C") (pinfunction "A_C") (pintype "passive"))
    )
    (net (code "28") (name "Net-(D2-C)") (class "Default")
      (node (ref "D2") (pin "A") (pinfunction "C_A") (pintype "passive"))
      (node (ref "J1") (pin "PWR") (pinfunction "PWR_PWR") (pintype "bidirectional"))
    )
    (net (code "29") (name "Net-(J3-Pad1)") (class "Default")
      (node (ref "J3") (pin "1") (pinfunction "1_1") (pintype "passive"))
      (node (ref "J3") (pin "2") (pinfunction "2_2") (pintype "passive"))
      (node (ref "J3") (pin "3") (pinfunction "3_3") (pintype "passive"))
      (node (ref "J3") (pin "4") (pinfunction "4_4") (pintype "passive"))
      (node (ref "J3") (pin "5") (pinfunction "5_5") (pintype "passive"))
      (node (ref "J4") (pin "1") (pinfunction "1_1") (pintype "passive"))
      (node (ref "J4") (pin "2") (pinfunction "2_2") (pintype "passive"))
      (node (ref "J4") (pin "3") (pinfunction "3_3") (pintype "passive"))
      (node (ref "J4") (pin "4") (pinfunction "4_4") (pintype "passive"))
      (node (ref "J4") (pin "5") (pinfunction "5_5") (pintype "passive"))
    )
    (net (code "30") (name "Net-(J5-Pad1)") (class "Default")
      (node (ref "J5") (pin "1") (pinfunction "1_1") (pintype "passive"))
      (node (ref "J5") (pin "2") (pinfunction "2_2") (pintype "passive"))
      (node (ref "J5") (pin "3") (pinfunction "3_3") (pintype "passive"))
      (node (ref "J5") (pin "4") (pinfunction "4_4") (pintype "passive"))
      (node (ref "J5") (pin "5") (pinfunction "5_5") (pintype "passive"))
      (node (ref "J65") (pin "1") (pinfunction "1_1") (pintype "passive"))
      (node (ref "J65") (pin "2") (pinfunction "2_2") (pintype "passive"))
      (node (ref "J65") (pin "3") (pinfunction "3_3") (pintype "passive"))
      (node (ref "J65") (pin "4") (pinfunction "4_4") (pintype "passive"))
      (node (ref "J65") (pin "5") (pinfunction "5_5") (pintype "passive"))
    )
    (net (code "31") (name "Net-(J6-Pad1)") (class "Default")
      (node (ref "J6") (pin "1") (pinfunction "1_1") (pintype "passive"))
      (node (ref "J6") (pin "2") (pinfunction "2_2") (pintype "passive"))
      (node (ref "J6") (pin "3") (pinfunction "3_3") (pintype "passive"))
      (node (ref "J6") (pin "4") (pinfunction "4_4") (pintype "passive"))
      (node (ref "J6") (pin "5") (pinfunction "5_5") (pintype "passive"))
      (node (ref "J7") (pin "1") (pinfunction "1_1") (pintype "passive"))
      (node (ref "J7") (pin "2") (pinfunction "2_2") (pintype "passive"))
      (node (ref "J7") (pin "3") (pinfunction "3_3") (pintype "passive"))
      (node (ref "J7") (pin "4") (pinfunction "4_4") (pintype "passive"))
      (node (ref "J7") (pin "5") (pinfunction "5_5") (pintype "passive"))
    )
    (net (code "32") (name "Net-(J8-Pad1)") (class "Default")
      (node (ref "J8") (pin "1") (pinfunction "1_1") (pintype "passive"))
      (node (ref "J8") (pin "2") (pinfunction "2_2") (pintype "passive"))
      (node (ref "J8") (pin "3") (pinfunction "3_3") (pintype "passive"))
      (node (ref "J8") (pin "4") (pinfunction "4_4") (pintype "passive"))
      (node (ref "J8") (pin "5") (pinfunction "5_5") (pintype "passive"))
      (node (ref "J9") (pin "1") (pinfunction "1_1") (pintype "passive"))
      (node (ref "J9") (pin "2") (pinfunction "2_2") (pintype "passive"))
      (node (ref "J9") (pin "3") (pinfunction "3_3") (pintype "passive"))
      (node (ref "J9") (pin "4") (pinfunction "4_4") (pintype "passive"))
      (node (ref "J9") (pin "5") (pinfunction "5_5") (pintype "passive"))
    )
    (net (code "33") (name "Net-(J10-Pad1)") (class "Default")
      (node (ref "J10") (pin "1") (pinfunction "1_1") (pintype "passive"))
      (node (ref "J10") (pin "2") (pinfunction "2_2") (pintype "passive"))
      (node (ref "J10") (pin "3") (pinfunction "3_3") (pintype "passive"))
      (node (ref "J10") (pin "4") (pinfunction "4_4") (pintype "passive"))
      (node (ref "J10") (pin "5") (pinfunction "5_5") (pintype "passive"))
      (node (ref "J11") (pin "1") (pinfunction "1_1") (pintype "passive"))
      (node (ref "J11") (pin "2") (pinfunction "2_2") (pintype "passive"))
      (node (ref "J11") (pin "3") (pinfunction "3_3") (pintype "passive"))
      (node (ref "J11") (pin "4") (pinfunction "4_4") (pintype "passive"))
      (node (ref "J11") (pin "5") (pinfunction "5_5") (pintype "passive"))
    )
    (net (code "34") (name "Net-(J12-Pad1)") (class "Default")
      (node (ref "J12") (pin "1") (pinfunction "1_1") (pintype "passive"))
      (node (ref "J12") (pin "2") (pinfunction "2_2") (pintype "passive"))
      (node (ref "J12") (pin "3") (pinfunction "3_3") (pintype "passive"))
      (node (ref "J12") (pin "4") (pinfunction "4_4") (pintype "passive"))
      (node (ref "J12") (pin "5") (pinfunction "5_5") (pintype "passive"))
      (node (ref "J70") (pin "1") (pinfunction "1_1") (pintype "passive"))
      (node (ref "J70") (pin "2") (pinfunction "2_2") (pintype "passive"))
      (node (ref "J70") (pin "3") (pinfunction "3_3") (pintype "passive"))
      (node (ref "J70") (pin "4") (pinfunction "4_4") (pintype "passive"))
      (node (ref "J70") (pin "5") (pinfunction "5_5") (pintype "passive"))
    )
    (net (code "35") (name "Net-(J13-Pad1)") (class "Default")
      (node (ref "J13") (pin "1") (pinfunction "1_1") (pintype "passive"))
      (node (ref "J13") (pin "2") (pinfunction "2_2") (pintype "passive"))
      (node (ref "J13") (pin "3") (pinfunction "3_3") (pintype "passive"))
      (node (ref "J13") (pin "4") (pinfunction "4_4") (pintype "passive"))
      (node (ref "J13") (pin "5") (pinfunction "5_5") (pintype "passive"))
      (node (ref "J22") (pin "1") (pinfunction "1_1") (pintype "passive"))
      (node (ref "J22") (pin "2") (pinfunction "2_2") (pintype "passive"))
      (node (ref "J22") (pin "3") (pinfunction "3_3") (pintype "passive"))
      (node (ref "J22") (pin "4") (pinfunction "4_4") (pintype "passive"))
      (node (ref "J22") (pin "5") (pinfunction "5_5") (pintype "passive"))
    )
    (net (code "36") (name "Net-(J14-Pad1)") (class "Default")
      (node (ref "J14") (pin "1") (pinfunction "1_1") (pintype "passive"))
      (node (ref "J14") (pin "2") (pinfunction "2_2") (pintype "passive"))
      (node (ref "J14") (pin "3") (pinfunction "3_3") (pintype "passive"))
      (node (ref "J14") (pin "4") (pinfunction "4_4") (pintype "passive"))
      (node (ref "J14") (pin "5") (pinfunction "5_5") (pintype "passive"))
      (node (ref "J31") (pin "1") (pinfunction "1_1") (pintype "passive"))
      (node (ref "J31") (pin "2") (pinfunction "2_2") (pintype "passive"))
      (node (ref "J31") (pin "3") (pinfunction "3_3") (pintype "passive"))
      (node (ref "J31") (pin "4") (pinfunction "4_4") (pintype "passive"))
      (node (ref "J31") (pin "5") (pinfunction "5_5") (pintype "passive"))
    )
    (net (code "37") (name "Net-(J15-Pad1)") (class "Default")
      (node (ref "J15") (pin "1") (pinfunction "1_1") (pintype "passive"))
      (node (ref "J15") (pin "2") (pinfunction "2_2") (pintype "passive"))
      (node (ref "J15") (pin "3") (pinfunction "3_3") (pintype "passive"))
      (node (ref "J15") (pin "4") (pinfunction "4_4") (pintype "passive"))
      (node (ref "J15") (pin "5") (pinfunction "5_5") (pintype "passive"))
      (node (ref "J21") (pin "1") (pinfunction "1_1") (pintype "passive"))
      (node (ref "J21") (pin "2") (pinfunction "2_2") (pintype "passive"))
      (node (ref "J21") (pin "3") (pinfunction "3_3") (pintype "passive"))
      (node (ref "J21") (pin "4") (pinfunction "4_4") (pintype "passive"))
      (node (ref "J21") (pin "5") (pinfunction "5_5") (pintype "passive"))
    )
    (net (code "38") (name "Net-(J16-Pad1)") (class "Default")
      (node (ref "J16") (pin "1") (pinfunction "1_1") (pintype "passive"))
      (node (ref "J16") (pin "2") (pinfunction "2_2") (pintype "passive"))
      (node (ref "J16") (pin "3") (pinfunction "3_3") (pintype "passive"))
      (node (ref "J16") (pin "4") (pinfunction "4_4") (pintype "passive"))
      (node (ref "J16") (pin "5") (pinfunction "5_5") (pintype "passive"))
      (node (ref "J29") (pin "1") (pinfunction "1_1") (pintype "passive"))
      (node (ref "J29") (pin "2") (pinfunction "2_2") (pintype "passive"))
      (node (ref "J29") (pin "3") (pinfunction "3_3") (pintype "passive"))
      (node (ref "J29") (pin "4") (pinfunction "4_4") (pintype "passive"))
      (node (ref "J29") (pin "5") (pinfunction "5_5") (pintype "passive"))
    )
    (net (code "39") (name "Net-(J17-Pad1)") (class "Default")
      (node (ref "J17") (pin "1") (pinfunction "1_1") (pintype "passive"))
      (node (ref "J17") (pin "2") (pinfunction "2_2") (pintype "passive"))
      (node (ref "J17") (pin "3") (pinfunction "3_3") (pintype "passive"))
      (node (ref "J17") (pin "4") (pinfunction "4_4") (pintype "passive"))
      (node (ref "J17") (pin "5") (pinfunction "5_5") (pintype "passive"))
      (node (ref "J30") (pin "1") (pinfunction "1_1") (pintype "passive"))
      (node (ref "J30") (pin "2") (pinfunction "2_2") (pintype "passive"))
      (node (ref "J30") (pin "3") (pinfunction "3_3") (pintype "passive"))
      (node (ref "J30") (pin "4") (pinfunction "4_4") (pintype "passive"))
      (node (ref "J30") (pin "5") (pinfunction "5_5") (pintype "passive"))
    )
    (net (code "40") (name "Net-(J18-Pad1)") (class "Default")
      (node (ref "J18") (pin "1") (pinfunction "1_1") (pintype "passive"))
      (node (ref "J18") (pin "2") (pinfunction "2_2") (pintype "passive"))
      (node (ref "J18") (pin "3") (pinfunction "3_3") (pintype "passive"))
      (node (ref "J18") (pin "4") (pinfunction "4_4") (pintype "passive"))
      (node (ref "J18") (pin "5") (pinfunction "5_5") (pintype "passive"))
      (node (ref "J19") (pin "1") (pinfunction "1_1") (pintype "passive"))
      (node (ref "J19") (pin "2") (pinfunction "2_2") (pintype "passive"))
      (node (ref "J19") (pin "3") (pinfunction "3_3") (pintype "passive"))
      (node (ref "J19") (pin "4") (pinfunction "4_4") (pintype "passive"))
      (node (ref "J19") (pin "5") (pinfunction "5_5") (pintype "passive"))
    )
    (net (code "41") (name "Net-(J20-Pad1)") (class "Default")
      (node (ref "J20") (pin "1") (pinfunction "1_1") (pintype "passive"))
      (node (ref "J20") (pin "2") (pinfunction "2_2") (pintype "passive"))
      (node (ref "J20") (pin "3") (pinfunction "3_3") (pintype "passive"))
      (node (ref "J20") (pin "4") (pinfunction "4_4") (pintype "passive"))
      (node (ref "J20") (pin "5") (pinfunction "5_5") (pintype "passive"))
      (node (ref "J26") (pin "1") (pinfunction "1_1") (pintype "passive"))
      (node (ref "J26") (pin "2") (pinfunction "2_2") (pintype "passive"))
      (node (ref "J26") (pin "3") (pinfunction "3_3") (pintype "passive"))
      (node (ref "J26") (pin "4") (pinfunction "4_4") (pintype "passive"))
      (node (ref "J26") (pin "5") (pinfunction "5_5") (pintype "passive"))
    )
    (net (code "42") (name "Net-(J23-Pad1)") (class "Default")
      (node (ref "J23") (pin "1") (pinfunction "1_1") (pintype "passive"))
      (node (ref "J23") (pin "2") (pinfunction "2_2") (pintype "passive"))
      (node (ref "J23") (pin "3") (pinfunction "3_3") (pintype "passive"))
      (node (ref "J23") (pin "4") (pinfunction "4_4") (pintype "passive"))
      (node (ref "J23") (pin "5") (pinfunction "5_5") (pintype "passive"))
      (node (ref "J32") (pin "1") (pinfunction "1_1") (pintype "passive"))
      (node (ref "J32") (pin "2") (pinfunction "2_2") (pintype "passive"))
      (node (ref "J32") (pin "3") (pinfunction "3_3") (pintype "passive"))
      (node (ref "J32") (pin "4") (pinfunction "4_4") (pintype "passive"))
      (node (ref "J32") (pin "5") (pinfunction "5_5") (pintype "passive"))
    )
    (net (code "43") (name "Net-(J24-Pad1)") (class "Default")
      (node (ref "J24") (pin "1") (pinfunction "1_1") (pintype "passive"))
      (node (ref "J24") (pin "2") (pinfunction "2_2") (pintype "passive"))
      (node (ref "J24") (pin "3") (pinfunction "3_3") (pintype "passive"))
      (node (ref "J24") (pin "4") (pinfunction "4_4") (pintype "passive"))
      (node (ref "J24") (pin "5") (pinfunction "5_5") (pintype "passive"))
      (node (ref "J33") (pin "1") (pinfunction "1_1") (pintype "passive"))
      (node (ref "J33") (pin "2") (pinfunction "2_2") (pintype "passive"))
      (node (ref "J33") (pin "3") (pinfunction "3_3") (pintype "passive"))
      (node (ref "J33") (pin "4") (pinfunction "4_4") (pintype "passive"))
      (node (ref "J33") (pin "5") (pinfunction "5_5") (pintype "passive"))
    )
    (net (code "44") (name "Net-(J25-Pad1)") (class "Default")
      (node (ref "J25") (pin "1") (pinfunction "1_1") (pintype "passive"))
      (node (ref "J25") (pin "2") (pinfunction "2_2") (pintype "passive"))
      (node (ref "J25") (pin "3") (pinfunction "3_3") (pintype "passive"))
      (node (ref "J25") (pin "4") (pinfunction "4_4") (pintype "passive"))
      (node (ref "J25") (pin "5") (pinfunction "5_5") (pintype "passive"))
      (node (ref "J41") (pin "1") (pinfunction "1_1") (pintype "passive"))
      (node (ref "J41") (pin "2") (pinfunction "2_2") (pintype "passive"))
      (node (ref "J41") (pin "3") (pinfunction "3_3") (pintype "passive"))
      (node (ref "J41") (pin "4") (pinfunction "4_4") (pintype "passive"))
      (node (ref "J41") (pin "5") (pinfunction "5_5") (pintype "passive"))
    )
    (net (code "45") (name "Net-(J27-Pad1)") (class "Default")
      (node (ref "J27") (pin "1") (pinfunction "1_1") (pintype "passive"))
      (node (ref "J27") (pin "2") (pinfunction "2_2") (pintype "passive"))
      (node (ref "J27") (pin "3") (pinfunction "3_3") (pintype "passive"))
      (node (ref "J27") (pin "4") (pinfunction "4_4") (pintype "passive"))
      (node (ref "J27") (pin "5") (pinfunction "5_5") (pintype "passive"))
      (node (ref "J28") (pin "1") (pinfunction "1_1") (pintype "passive"))
      (node (ref "J28") (pin "2") (pinfunction "2_2") (pintype "passive"))
      (node (ref "J28") (pin "3") (pinfunction "3_3") (pintype "passive"))
      (node (ref "J28") (pin "4") (pinfunction "4_4") (pintype "passive"))
      (node (ref "J28") (pin "5") (pinfunction "5_5") (pintype "passive"))
    )
    (net (code "46") (name "Net-(J34-Pad1)") (class "Default")
      (node (ref "J34") (pin "1") (pinfunction "1_1") (pintype "passive"))
      (node (ref "J34") (pin "2") (pinfunction "2_2") (pintype "passive"))
      (node (ref "J34") (pin "3") (pinfunction "3_3") (pintype "passive"))
      (node (ref "J34") (pin "4") (pinfunction "4_4") (pintype "passive"))
      (node (ref "J34") (pin "5") (pinfunction "5_5") (pintype "passive"))
      (node (ref "J35") (pin "1") (pinfunction "1_1") (pintype "passive"))
      (node (ref "J35") (pin "2") (pinfunction "2_2") (pintype "passive"))
      (node (ref "J35") (pin "3") (pinfunction "3_3") (pintype "passive"))
      (node (ref "J35") (pin "4") (pinfunction "4_4") (pintype "passive"))
      (node (ref "J35") (pin "5") (pinfunction "5_5") (pintype "passive"))
    )
    (net (code "47") (name "Net-(J36-Pad1)") (class "Default")
      (node (ref "J36") (pin "1") (pinfunction "1_1") (pintype "passive"))
      (node (ref "J36") (pin "2") (pinfunction "2_2") (pintype "passive"))
      (node (ref "J36") (pin "3") (pinfunction "3_3") (pintype "passive"))
      (node (ref "J36") (pin "4") (pinfunction "4_4") (pintype "passive"))
      (node (ref "J36") (pin "5") (pinfunction "5_5") (pintype "passive"))
      (node (ref "J42") (pin "1") (pinfunction "1_1") (pintype "passive"))
      (node (ref "J42") (pin "2") (pinfunction "2_2") (pintype "passive"))
      (node (ref "J42") (pin "3") (pinfunction "3_3") (pintype "passive"))
      (node (ref "J42") (pin "4") (pinfunction "4_4") (pintype "passive"))
      (node (ref "J42") (pin "5") (pinfunction "5_5") (pintype "passive"))
    )
    (net (code "48") (name "Net-(J37-Pad1)") (class "Default")
      (node (ref "J37") (pin "1") (pinfunction "1_1") (pintype "passive"))
      (node (ref "J37") (pin "2") (pinfunction "2_2") (pintype "passive"))
      (node (ref "J37") (pin "3") (pinfunction "3_3") (pintype "passive"))
      (node (ref "J37") (pin "4") (pinfunction "4_4") (pintype "passive"))
      (node (ref "J37") (pin "5") (pinfunction "5_5") (pintype "passive"))
      (node (ref "J71") (pin "1") (pinfunction "1_1") (pintype "passive"))
      (node (ref "J71") (pin "2") (pinfunction "2_2") (pintype "passive"))
      (node (ref "J71") (pin "3") (pinfunction "3_3") (pintype "passive"))
      (node (ref "J71") (pin "4") (pinfunction "4_4") (pintype "passive"))
      (node (ref "J71") (pin "5") (pinfunction "5_5") (pintype "passive"))
    )
    (net (code "49") (name "Net-(J38-Pad1)") (class "Default")
      (node (ref "J38") (pin "1") (pinfunction "1_1") (pintype "passive"))
      (node (ref "J38") (pin "2") (pinfunction "2_2") (pintype "passive"))
      (node (ref "J38") (pin "3") (pinfunction "3_3") (pintype "passive"))
      (node (ref "J38") (pin "4") (pinfunction "4_4") (pintype "passive"))
      (node (ref "J38") (pin "5") (pinfunction "5_5") (pintype "passive"))
      (node (ref "J72") (pin "1") (pinfunction "1_1") (pintype "passive"))
      (node (ref "J72") (pin "2") (pinfunction "2_2") (pintype "passive"))
      (node (ref "J72") (pin "3") (pinfunction "3_3") (pintype "passive"))
      (node (ref "J72") (pin "4") (pinfunction "4_4") (pintype "passive"))
      (node (ref "J72") (pin "5") (pinfunction "5_5") (pintype "passive"))
    )
    (net (code "50") (name "Net-(J39-Pad1)") (class "Default")
      (node (ref "J39") (pin "1") (pinfunction "1_1") (pintype "passive"))
      (node (ref "J39") (pin "2") (pinfunction "2_2") (pintype "passive"))
      (node (ref "J39") (pin "3") (pinfunction "3_3") (pintype "passive"))
      (node (ref "J39") (pin "4") (pinfunction "4_4") (pintype "passive"))
      (node (ref "J39") (pin "5") (pinfunction "5_5") (pintype "passive"))
      (node (ref "J40") (pin "1") (pinfunction "1_1") (pintype "passive"))
      (node (ref "J40") (pin "2") (pinfunction "2_2") (pintype "passive"))
      (node (ref "J40") (pin "3") (pinfunction "3_3") (pintype "passive"))
      (node (ref "J40") (pin "4") (pinfunction "4_4") (pintype "passive"))
      (node (ref "J40") (pin "5") (pinfunction "5_5") (pintype "passive"))
    )
    (net (code "51") (name "Net-(J43-Pad1)") (class "Default")
      (node (ref "J43") (pin "1") (pinfunction "1_1") (pintype "passive"))
      (node (ref "J43") (pin "2") (pinfunction "2_2") (pintype "passive"))
      (node (ref "J43") (pin "3") (pinfunction "3_3") (pintype "passive"))
      (node (ref "J43") (pin "4") (pinfunction "4_4") (pintype "passive"))
      (node (ref "J43") (pin "5") (pinfunction "5_5") (pintype "passive"))
      (node (ref "J44") (pin "1") (pinfunction "1_1") (pintype "passive"))
      (node (ref "J44") (pin "2") (pinfunction "2_2") (pintype "passive"))
      (node (ref "J44") (pin "3") (pinfunction "3_3") (pintype "passive"))
      (node (ref "J44") (pin "4") (pinfunction "4_4") (pintype "passive"))
      (node (ref "J44") (pin "5") (pinfunction "5_5") (pintype "passive"))
    )
    (net (code "52") (name "Net-(J45-Pad1)") (class "Default")
      (node (ref "J45") (pin "1") (pinfunction "1_1") (pintype "passive"))
      (node (ref "J45") (pin "2") (pinfunction "2_2") (pintype "passive"))
      (node (ref "J45") (pin "3") (pinfunction "3_3") (pintype "passive"))
      (node (ref "J45") (pin "4") (pinfunction "4_4") (pintype "passive"))
      (node (ref "J45") (pin "5") (pinfunction "5_5") (pintype "passive"))
      (node (ref "J46") (pin "1") (pinfunction "1_1") (pintype "passive"))
      (node (ref "J46") (pin "2") (pinfunction "2_2") (pintype "passive"))
      (node (ref "J46") (pin "3") (pinfunction "3_3") (pintype "passive"))
      (node (ref "J46") (pin "4") (pinfunction "4_4") (pintype "passive"))
      (node (ref "J46") (pin "5") (pinfunction "5_5") (pintype "passive"))
    )
    (net (code "53") (name "Net-(J47-Pad1)") (class "Default")
      (node (ref "J47") (pin "1") (pinfunction "1_1") (pintype "passive"))
      (node (ref "J47") (pin "2") (pinfunction "2_2") (pintype "passive"))
      (node (ref "J47") (pin "3") (pinfunction "3_3") (pintype "passive"))
      (node (ref "J47") (pin "4") (pinfunction "4_4") (pintype "passive"))
      (node (ref "J47") (pin "5") (pinfunction "5_5") (pintype "passive"))
      (node (ref "J48") (pin "1") (pinfunction "1_1") (pintype "passive"))
      (node (ref "J48") (pin "2") (pinfunction "2_2") (pintype "passive"))
      (node (ref "J48") (pin "3") (pinfunction "3_3") (pintype "passive"))
      (node (ref "J48") (pin "4") (pinfunction "4_4") (pintype "passive"))
      (node (ref "J48") (pin "5") (pinfunction "5_5") (pintype "passive"))
    )
    (net (code "54") (name "Net-(J49-Pad1)") (class "Default")
      (node (ref "J49") (pin "1") (pinfunction "1_1") (pintype "passive"))
      (node (ref "J49") (pin "2") (pinfunction "2_2") (pintype "passive"))
      (node (ref "J49") (pin "3") (pinfunction "3_3") (pintype "passive"))
      (node (ref "J49") (pin "4") (pinfunction "4_4") (pintype "passive"))
      (node (ref "J49") (pin "5") (pinfunction "5_5") (pintype "passive"))
      (node (ref "J53") (pin "1") (pinfunction "1_1") (pintype "passive"))
      (node (ref "J53") (pin "2") (pinfunction "2_2") (pintype "passive"))
      (node (ref "J53") (pin "3") (pinfunction "3_3") (pintype "passive"))
      (node (ref "J53") (pin "4") (pinfunction "4_4") (pintype "passive"))
      (node (ref "J53") (pin "5") (pinfunction "5_5") (pintype "passive"))
    )
    (net (code "55") (name "Net-(J50-Pad1)") (class "Default")
      (node (ref "J50") (pin "1") (pinfunction "1_1") (pintype "passive"))
      (node (ref "J50") (pin "2") (pinfunction "2_2") (pintype "passive"))
      (node (ref "J50") (pin "3") (pinfunction "3_3") (pintype "passive"))
      (node (ref "J50") (pin "4") (pinfunction "4_4") (pintype "passive"))
      (node (ref "J50") (pin "5") (pinfunction "5_5") (pintype "passive"))
      (node (ref "J51") (pin "1") (pinfunction "1_1") (pintype "passive"))
      (node (ref "J51") (pin "2") (pinfunction "2_2") (pintype "passive"))
      (node (ref "J51") (pin "3") (pinfunction "3_3") (pintype "passive"))
      (node (ref "J51") (pin "4") (pinfunction "4_4") (pintype "passive"))
      (node (ref "J51") (pin "5") (pinfunction "5_5") (pintype "passive"))
    )
    (net (code "56") (name "Net-(J52-Pad1)") (class "Default")
      (node (ref "J52") (pin "1") (pinfunction "1_1") (pintype "passive"))
      (node (ref "J52") (pin "2") (pinfunction "2_2") (pintype "passive"))
      (node (ref "J52") (pin "3") (pinfunction "3_3") (pintype "passive"))
      (node (ref "J52") (pin "4") (pinfunction "4_4") (pintype "passive"))
      (node (ref "J52") (pin "5") (pinfunction "5_5") (pintype "passive"))
      (node (ref "J58") (pin "1") (pinfunction "1_1") (pintype "passive"))
      (node (ref "J58") (pin "2") (pinfunction "2_2") (pintype "passive"))
      (node (ref "J58") (pin "3") (pinfunction "3_3") (pintype "passive"))
      (node (ref "J58") (pin "4") (pinfunction "4_4") (pintype "passive"))
      (node (ref "J58") (pin "5") (pinfunction "5_5") (pintype "passive"))
    )
    (net (code "57") (name "Net-(J54-Pad1)") (class "Default")
      (node (ref "J54") (pin "1") (pinfunction "1_1") (pintype "passive"))
      (node (ref "J54") (pin "2") (pinfunction "2_2") (pintype "passive"))
      (node (ref "J54") (pin "3") (pinfunction "3_3") (pintype "passive"))
      (node (ref "J54") (pin "4") (pinfunction "4_4") (pintype "passive"))
      (node (ref "J54") (pin "5") (pinfunction "5_5") (pintype "passive"))
      (node (ref "J61") (pin "1") (pinfunction "1_1") (pintype "passive"))
      (node (ref "J61") (pin "2") (pinfunction "2_2") (pintype "passive"))
      (node (ref "J61") (pin "3") (pinfunction "3_3") (pintype "passive"))
      (node (ref "J61") (pin "4") (pinfunction "4_4") (pintype "passive"))
      (node (ref "J61") (pin "5") (pinfunction "5_5") (pintype "passive"))
    )
    (net (code "58") (name "Net-(J55-Pad1)") (class "Default")
      (node (ref "J55") (pin "1") (pinfunction "1_1") (pintype "passive"))
      (node (ref "J55") (pin "2") (pinfunction "2_2") (pintype "passive"))
      (node (ref "J55") (pin "3") (pinfunction "3_3") (pintype "passive"))
      (node (ref "J55") (pin "4") (pinfunction "4_4") (pintype "passive"))
      (node (ref "J55") (pin "5") (pinfunction "5_5") (pintype "passive"))
      (node (ref "J56") (pin "1") (pinfunction "1_1") (pintype "passive"))
      (node (ref "J56") (pin "2") (pinfunction "2_2") (pintype "passive"))
      (node (ref "J56") (pin "3") (pinfunction "3_3") (pintype "passive"))
      (node (ref "J56") (pin "4") (pinfunction "4_4") (pintype "passive"))
      (node (ref "J56") (pin "5") (pinfunction "5_5") (pintype "passive"))
    )
    (net (code "59") (name "Net-(J57-Pad1)") (class "Default")
      (node (ref "J57") (pin "1") (pinfunction "1_1") (pintype "passive"))
      (node (ref "J57") (pin "2") (pinfunction "2_2") (pintype "passive"))
      (node (ref "J57") (pin "3") (pinfunction "3_3") (pintype "passive"))
      (node (ref "J57") (pin "4") (pinfunction "4_4") (pintype "passive"))
      (node (ref "J57") (pin "5") (pinfunction "5_5") (pintype "passive"))
      (node (ref "J62") (pin "1") (pinfunction "1_1") (pintype "passive"))
      (node (ref "J62") (pin "2") (pinfunction "2_2") (pintype "passive"))
      (node (ref "J62") (pin "3") (pinfunction "3_3") (pintype "passive"))
      (node (ref "J62") (pin "4") (pinfunction "4_4") (pintype "passive"))
      (node (ref "J62") (pin "5") (pinfunction "5_5") (pintype "passive"))
    )
    (net (code "60") (name "Net-(J59-Pad1)") (class "Default")
      (node (ref "J59") (pin "1") (pinfunction "1_1") (pintype "passive"))
      (node (ref "J59") (pin "2") (pinfunction "2_2") (pintype "passive"))
      (node (ref "J59") (pin "3") (pinfunction "3_3") (pintype "passive"))
      (node (ref "J59") (pin "4") (pinfunction "4_4") (pintype "passive"))
      (node (ref "J59") (pin "5") (pinfunction "5_5") (pintype "passive"))
      (node (ref "J60") (pin "1") (pinfunction "1_1") (pintype "passive"))
      (node (ref "J60") (pin "2") (pinfunction "2_2") (pintype "passive"))
      (node (ref "J60") (pin "3") (pinfunction "3_3") (pintype "passive"))
      (node (ref "J60") (pin "4") (pinfunction "4_4") (pintype "passive"))
      (node (ref "J60") (pin "5") (pinfunction "5_5") (pintype "passive"))
    )
    (net (code "61") (name "Net-(J63-Pad1)") (class "Default")
      (node (ref "J63") (pin "1") (pinfunction "1_1") (pintype "passive"))
      (node (ref "J63") (pin "2") (pinfunction "2_2") (pintype "passive"))
      (node (ref "J63") (pin "3") (pinfunction "3_3") (pintype "passive"))
      (node (ref "J63") (pin "4") (pinfunction "4_4") (pintype "passive"))
      (node (ref "J63") (pin "5") (pinfunction "5_5") (pintype "passive"))
      (node (ref "J64") (pin "1") (pinfunction "1_1") (pintype "passive"))
      (node (ref "J64") (pin "2") (pinfunction "2_2") (pintype "passive"))
      (node (ref "J64") (pin "3") (pinfunction "3_3") (pintype "passive"))
      (node (ref "J64") (pin "4") (pinfunction "4_4") (pintype "passive"))
      (node (ref "J64") (pin "5") (pinfunction "5_5") (pintype "passive"))
    )
    (net (code "62") (name "Net-(J66-Pad1)") (class "Default")
      (node (ref "J66") (pin "1") (pinfunction "1_1") (pintype "passive"))
      (node (ref "J66") (pin "2") (pinfunction "2_2") (pintype "passive"))
      (node (ref "J66") (pin "3") (pinfunction "3_3") (pintype "passive"))
      (node (ref "J66") (pin "4") (pinfunction "4_4") (pintype "passive"))
      (node (ref "J66") (pin "5") (pinfunction "5_5") (pintype "passive"))
      (node (ref "J69") (pin "1") (pinfunction "1_1") (pintype "passive"))
      (node (ref "J69") (pin "2") (pinfunction "2_2") (pintype "passive"))
      (node (ref "J69") (pin "3") (pinfunction "3_3") (pintype "passive"))
      (node (ref "J69") (pin "4") (pinfunction "4_4") (pintype "passive"))
      (node (ref "J69") (pin "5") (pinfunction "5_5") (pintype "passive"))
    )
    (net (code "63") (name "Net-(J67-Pad1)") (class "Default")
      (node (ref "J67") (pin "1") (pinfunction "1_1") (pintype "passive"))
      (node (ref "J67") (pin "2") (pinfunction "2_2") (pintype "passive"))
      (node (ref "J67") (pin "3") (pinfunction "3_3") (pintype "passive"))
      (node (ref "J67") (pin "4") (pinfunction "4_4") (pintype "passive"))
      (node (ref "J67") (pin "5") (pinfunction "5_5") (pintype "passive"))
      (node (ref "J68") (pin "1") (pinfunction "1_1") (pintype "passive"))
      (node (ref "J68") (pin "2") (pinfunction "2_2") (pintype "passive"))
      (node (ref "J68") (pin "3") (pinfunction "3_3") (pintype "passive"))
      (node (ref "J68") (pin "4") (pinfunction "4_4") (pintype "passive"))
      (node (ref "J68") (pin "5") (pinfunction "5_5") (pintype "passive"))
    )
    (net (code "64") (name "Net-(J73-Pad1)") (class "Default")
      (node (ref "J73") (pin "1") (pinfunction "1_1") (pintype "passive"))
      (node (ref "J73") (pin "2") (pinfunction "2_2") (pintype "passive"))
      (node (ref "J73") (pin "3") (pinfunction "3_3") (pintype "passive"))
      (node (ref "J73") (pin "4") (pinfunction "4_4") (pintype "passive"))
      (node (ref "J73") (pin "5") (pinfunction "5_5") (pintype "passive"))
      (node (ref "J74") (pin "1") (pinfunction "1_1") (pintype "passive"))
      (node (ref "J74") (pin "2") (pinfunction "2_2") (pintype "passive"))
      (node (ref "J74") (pin "3") (pinfunction "3_3") (pintype "passive"))
      (node (ref "J74") (pin "4") (pinfunction "4_4") (pintype "passive"))
      (node (ref "J74") (pin "5") (pinfunction "5_5") (pintype "passive"))
    )
    (net (code "65") (name "Net-(J76-Pad1)") (class "Default")
      (node (ref "J76") (pin "1") (pinfunction "1_1") (pintype "passive"))
      (node (ref "J76") (pin "2") (pinfunction "2_2") (pintype "passive"))
      (node (ref "J76") (pin "3") (pinfunction "3_3") (pintype "passive"))
      (node (ref "J76") (pin "4") (pinfunction "4_4") (pintype "passive"))
      (node (ref "J76") (pin "5") (pinfunction "5_5") (pintype "passive"))
      (node (ref "J77") (pin "1") (pinfunction "1_1") (pintype "passive"))
      (node (ref "J77") (pin "2") (pinfunction "2_2") (pintype "passive"))
      (node (ref "J77") (pin "3") (pinfunction "3_3") (pintype "passive"))
      (node (ref "J77") (pin "4") (pinfunction "4_4") (pintype "passive"))
      (node (ref "J77") (pin "5") (pinfunction "5_5") (pintype "passive"))
    )
    (net (code "66") (name "Net-(J78-Pad1)") (class "Default")
      (node (ref "J78") (pin "1") (pinfunction "1_1") (pintype "passive"))
      (node (ref "J78") (pin "2") (pinfunction "2_2") (pintype "passive"))
      (node (ref "J78") (pin "3") (pinfunction "3_3") (pintype "passive"))
      (node (ref "J78") (pin "4") (pinfunction "4_4") (pintype "passive"))
      (node (ref "J78") (pin "5") (pinfunction "5_5") (pintype "passive"))
      (node (ref "J79") (pin "1") (pinfunction "1_1") (pintype "passive"))
      (node (ref "J79") (pin "2") (pinfunction "2_2") (pintype "passive"))
      (node (ref "J79") (pin "3") (pinfunction "3_3") (pintype "passive"))
      (node (ref "J79") (pin "4") (pinfunction "4_4") (pintype "passive"))
      (node (ref "J79") (pin "5") (pinfunction "5_5") (pintype "passive"))
    )
    (net (code "67") (name "Net-(J87-Pad1)") (class "Default")
      (node (ref "J87") (pin "1") (pinfunction "1_1") (pintype "passive"))
      (node (ref "J87") (pin "2") (pinfunction "2_2") (pintype "passive"))
      (node (ref "J87") (pin "3") (pinfunction "3_3") (pintype "passive"))
      (node (ref "J87") (pin "4") (pinfunction "4_4") (pintype "passive"))
      (node (ref "J87") (pin "5") (pinfunction "5_5") (pintype "passive"))
      (node (ref "J88") (pin "1") (pinfunction "1_1") (pintype "passive"))
      (node (ref "J88") (pin "2") (pinfunction "2_2") (pintype "passive"))
      (node (ref "J88") (pin "3") (pinfunction "3_3") (pintype "passive"))
      (node (ref "J88") (pin "4") (pinfunction "4_4") (pintype "passive"))
      (node (ref "J88") (pin "5") (pinfunction "5_5") (pintype "passive"))
    )
    (net (code "68") (name "Net-(J89-Pad1)") (class "Default")
      (node (ref "J89") (pin "1") (pinfunction "1_1") (pintype "passive"))
      (node (ref "J89") (pin "2") (pinfunction "2_2") (pintype "passive"))
      (node (ref "J89") (pin "3") (pinfunction "3_3") (pintype "passive"))
      (node (ref "J89") (pin "4") (pinfunction "4_4") (pintype "passive"))
      (node (ref "J89") (pin "5") (pinfunction "5_5") (pintype "passive"))
      (node (ref "J90") (pin "1") (pinfunction "1_1") (pintype "passive"))
      (node (ref "J90") (pin "2") (pinfunction "2_2") (pintype "passive"))
      (node (ref "J90") (pin "3") (pinfunction "3_3") (pintype "passive"))
      (node (ref "J90") (pin "4") (pinfunction "4_4") (pintype "passive"))
      (node (ref "J90") (pin "5") (pinfunction "5_5") (pintype "passive"))
    )
    (net (code "69") (name "Net-(R1-1)") (class "Default")
      (node (ref "D1") (pin "A") (pinfunction "A_A") (pintype "passive"))
      (node (ref "R1") (pin "P$1") (pinfunction "1_P$1") (pintype "passive"))
    )
    (net (code "70") (name "Net-(R2-1)") (class "Default")
      (node (ref "7805") (pin "GND") (pinfunction "GND_GND") (pintype "input"))
      (node (ref "R2") (pin "P$1") (pinfunction "1_P$1") (pintype "passive"))
      (node (ref "R3") (pin "P$2") (pinfunction "2_P$2") (pintype "passive"))
    )
    (net (code "71") (name "Net-(U2-PB6(XTAL1{slash}TOSC1))") (class "Default")
      (node (ref "C2") (pin "2") (pinfunction "2_2") (pintype "passive"))
      (node (ref "U2") (pin "9") (pinfunction "PB6(XTAL1/TOSC1)_9") (pintype "bidirectional"))
      (node (ref "Y1") (pin "2") (pinfunction "2_2") (pintype "passive"))
    )
    (net (code "72") (name "Net-(U2-PB7(XTAL2{slash}TOSC2))") (class "Default")
      (node (ref "C5") (pin "2") (pinfunction "2_2") (pintype "passive"))
      (node (ref "U2") (pin "10") (pinfunction "PB7(XTAL2/TOSC2)_10") (pintype "bidirectional"))
      (node (ref "Y1") (pin "1") (pinfunction "1_1") (pintype "passive"))
    )
    (net (code "73") (name "unconnected-(POWER-Pad8)") (class "Default")
      (node (ref "POWER") (pin "8") (pinfunction "8_8") (pintype "passive"))
    )
  )
)
